# 4_ch_sample_and_hold.net
KiCad netlist of a schematic drawn in EAGLE
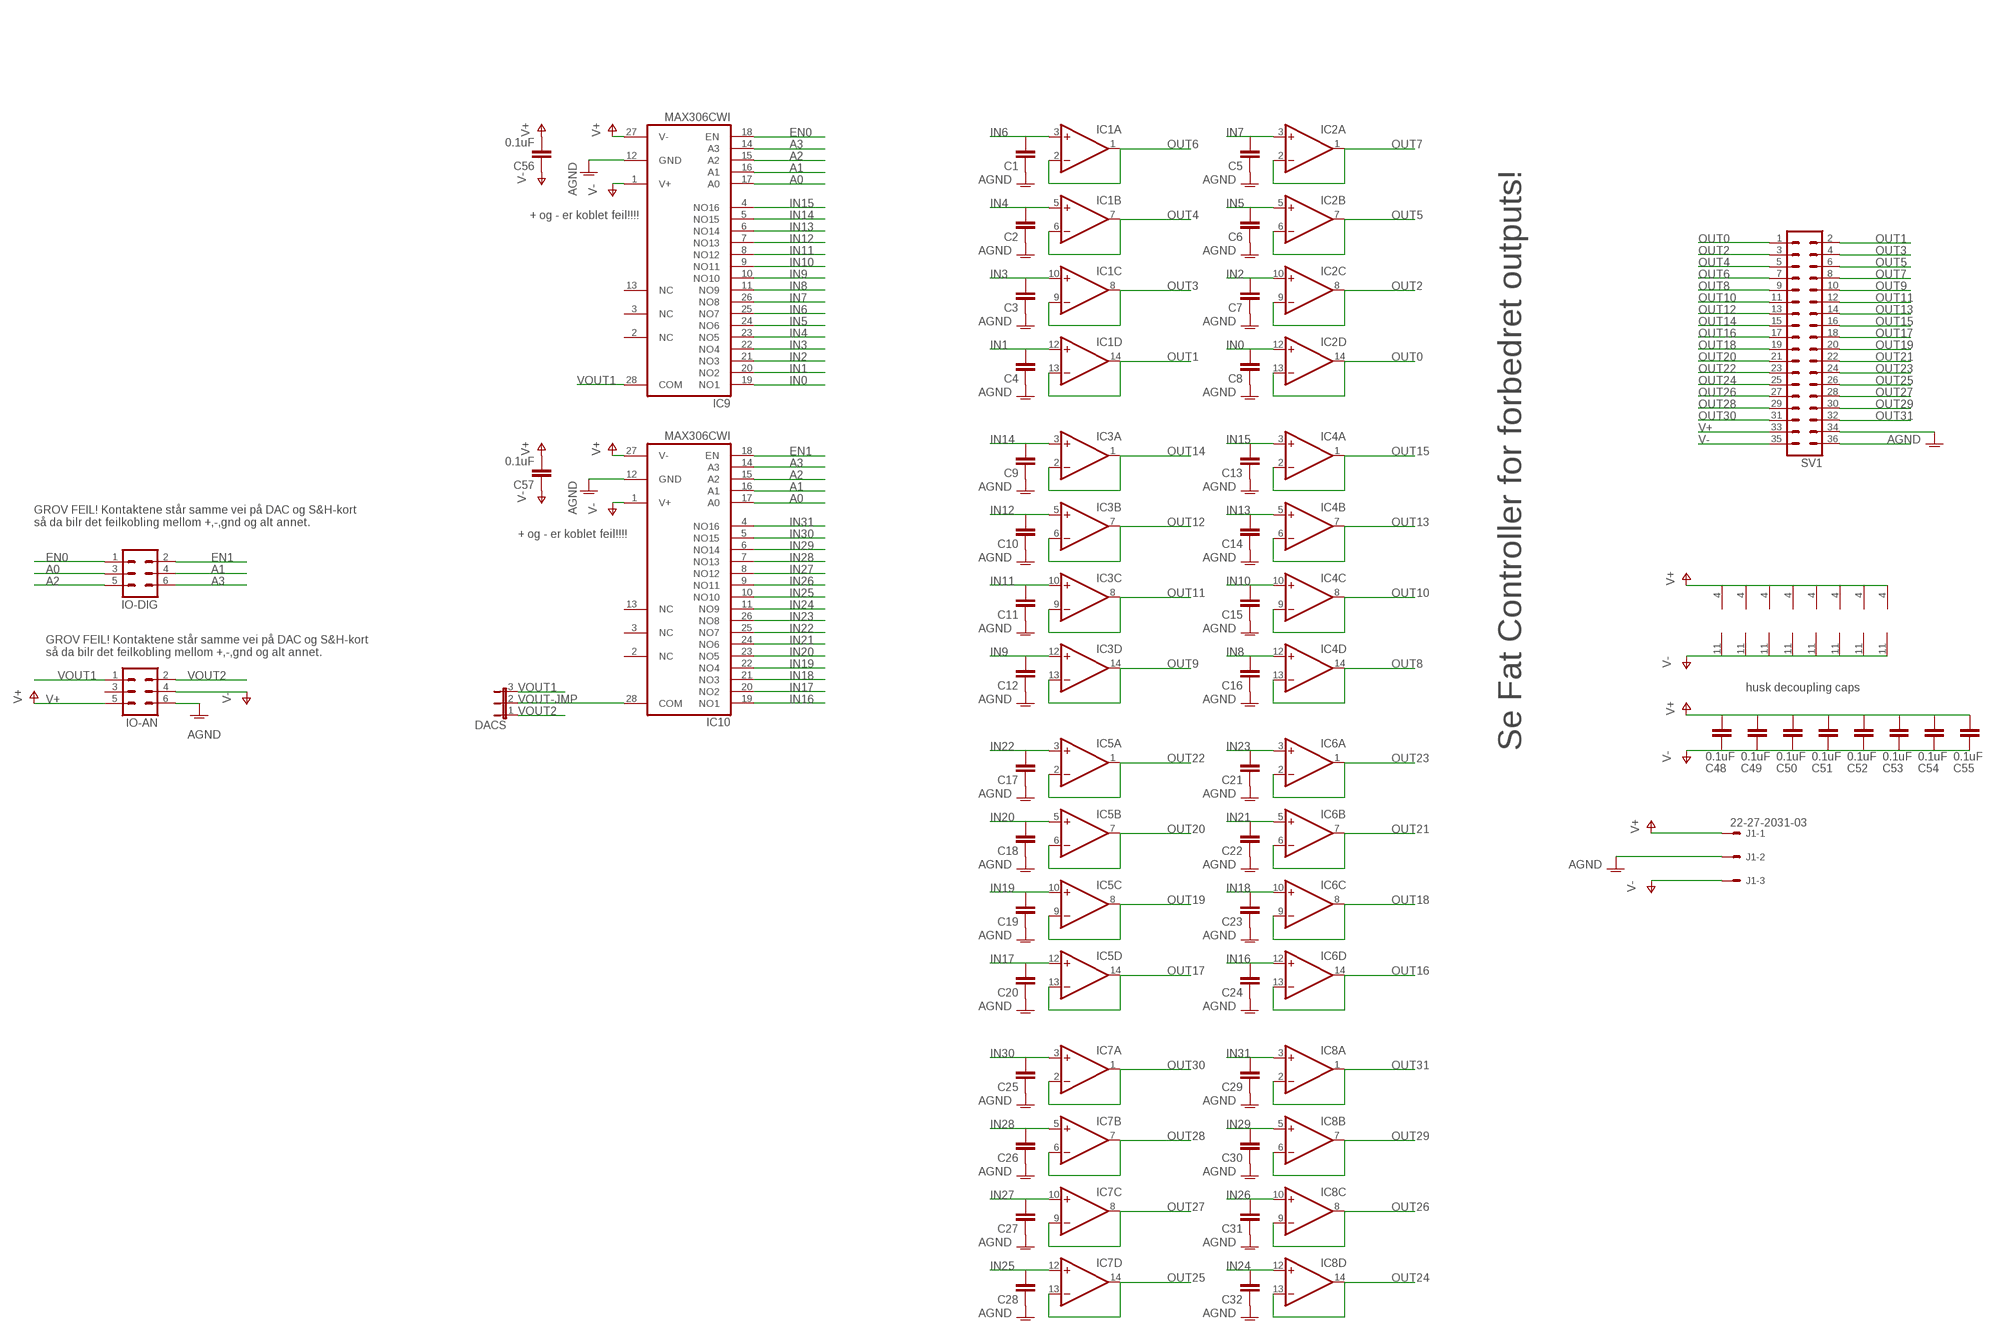
[diagram p0: schematic, sheet 1]

(export (version "E")
  (design (tool "Eeschema 10.0.6"))
  (components
    (comp (ref "C1")
      (value "C-EUC1206")
      (footprint "eagle-import:C1206")
      (libsource (lib "eagle-import") (part "C-EUC1206"))
    )
    (comp (ref "C2")
      (value "C-EUC1206")
      (footprint "eagle-import:C1206")
      (libsource (lib "eagle-import") (part "C-EUC1206"))
    )
    (comp (ref "C3")
      (value "C-EUC1206")
      (footprint "eagle-import:C1206")
      (libsource (lib "eagle-import") (part "C-EUC1206"))
    )
    (comp (ref "C4")
      (value "C-EUC1206")
      (footprint "eagle-import:C1206")
      (libsource (lib "eagle-import") (part "C-EUC1206"))
    )
    (comp (ref "C5")
      (value "C-EUC1206")
      (footprint "eagle-import:C1206")
      (libsource (lib "eagle-import") (part "C-EUC1206"))
    )
    (comp (ref "C6")
      (value "C-EUC1206")
      (footprint "eagle-import:C1206")
      (libsource (lib "eagle-import") (part "C-EUC1206"))
    )
    (comp (ref "C7")
      (value "C-EUC1206")
      (footprint "eagle-import:C1206")
      (libsource (lib "eagle-import") (part "C-EUC1206"))
    )
    (comp (ref "C8")
      (value "C-EUC1206")
      (footprint "eagle-import:C1206")
      (libsource (lib "eagle-import") (part "C-EUC1206"))
    )
    (comp (ref "C9")
      (value "C-EUC1206")
      (footprint "eagle-import:C1206")
      (libsource (lib "eagle-import") (part "C-EUC1206"))
    )
    (comp (ref "C10")
      (value "C-EUC1206")
      (footprint "eagle-import:C1206")
      (libsource (lib "eagle-import") (part "C-EUC1206"))
    )
    (comp (ref "C11")
      (value "C-EUC1206")
      (footprint "eagle-import:C1206")
      (libsource (lib "eagle-import") (part "C-EUC1206"))
    )
    (comp (ref "C12")
      (value "C-EUC1206")
      (footprint "eagle-import:C1206")
      (libsource (lib "eagle-import") (part "C-EUC1206"))
    )
    (comp (ref "C13")
      (value "C-EUC1206")
      (footprint "eagle-import:C1206")
      (libsource (lib "eagle-import") (part "C-EUC1206"))
    )
    (comp (ref "C14")
      (value "C-EUC1206")
      (footprint "eagle-import:C1206")
      (libsource (lib "eagle-import") (part "C-EUC1206"))
    )
    (comp (ref "C15")
      (value "C-EUC1206")
      (footprint "eagle-import:C1206")
      (libsource (lib "eagle-import") (part "C-EUC1206"))
    )
    (comp (ref "C16")
      (value "C-EUC1206")
      (footprint "eagle-import:C1206")
      (libsource (lib "eagle-import") (part "C-EUC1206"))
    )
    (comp (ref "C17")
      (value "C-EUC1206")
      (footprint "eagle-import:C1206")
      (libsource (lib "eagle-import") (part "C-EUC1206"))
    )
    (comp (ref "C18")
      (value "C-EUC1206")
      (footprint "eagle-import:C1206")
      (libsource (lib "eagle-import") (part "C-EUC1206"))
    )
    (comp (ref "C19")
      (value "C-EUC1206")
      (footprint "eagle-import:C1206")
      (libsource (lib "eagle-import") (part "C-EUC1206"))
    )
    (comp (ref "C20")
      (value "C-EUC1206")
      (footprint "eagle-import:C1206")
      (libsource (lib "eagle-import") (part "C-EUC1206"))
    )
    (comp (ref "C21")
      (value "C-EUC1206")
      (footprint "eagle-import:C1206")
      (libsource (lib "eagle-import") (part "C-EUC1206"))
    )
    (comp (ref "C22")
      (value "C-EUC1206")
      (footprint "eagle-import:C1206")
      (libsource (lib "eagle-import") (part "C-EUC1206"))
    )
    (comp (ref "C23")
      (value "C-EUC1206")
      (footprint "eagle-import:C1206")
      (libsource (lib "eagle-import") (part "C-EUC1206"))
    )
    (comp (ref "C24")
      (value "C-EUC1206")
      (footprint "eagle-import:C1206")
      (libsource (lib "eagle-import") (part "C-EUC1206"))
    )
    (comp (ref "C25")
      (value "C-EUC1206")
      (footprint "eagle-import:C1206")
      (libsource (lib "eagle-import") (part "C-EUC1206"))
    )
    (comp (ref "C26")
      (value "C-EUC1206")
      (footprint "eagle-import:C1206")
      (libsource (lib "eagle-import") (part "C-EUC1206"))
    )
    (comp (ref "C27")
      (value "C-EUC1206")
      (footprint "eagle-import:C1206")
      (libsource (lib "eagle-import") (part "C-EUC1206"))
    )
    (comp (ref "C28")
      (value "C-EUC1206")
      (footprint "eagle-import:C1206")
      (libsource (lib "eagle-import") (part "C-EUC1206"))
    )
    (comp (ref "C29")
      (value "C-EUC1206")
      (footprint "eagle-import:C1206")
      (libsource (lib "eagle-import") (part "C-EUC1206"))
    )
    (comp (ref "C30")
      (value "C-EUC1206")
      (footprint "eagle-import:C1206")
      (libsource (lib "eagle-import") (part "C-EUC1206"))
    )
    (comp (ref "C31")
      (value "C-EUC1206")
      (footprint "eagle-import:C1206")
      (libsource (lib "eagle-import") (part "C-EUC1206"))
    )
    (comp (ref "C32")
      (value "C-EUC1206")
      (footprint "eagle-import:C1206")
      (libsource (lib "eagle-import") (part "C-EUC1206"))
    )
    (comp (ref "C48")
      (value "0.1uF")
      (footprint "eagle-import:C0603")
      (libsource (lib "eagle-import") (part "C-EUC0603"))
    )
    (comp (ref "C49")
      (value "0.1uF")
      (footprint "eagle-import:C0603")
      (libsource (lib "eagle-import") (part "C-EUC0603"))
    )
    (comp (ref "C50")
      (value "0.1uF")
      (footprint "eagle-import:C0603")
      (libsource (lib "eagle-import") (part "C-EUC0603"))
    )
    (comp (ref "C51")
      (value "0.1uF")
      (footprint "eagle-import:C0603")
      (libsource (lib "eagle-import") (part "C-EUC0603"))
    )
    (comp (ref "C52")
      (value "0.1uF")
      (footprint "eagle-import:C0603")
      (libsource (lib "eagle-import") (part "C-EUC0603"))
    )
    (comp (ref "C53")
      (value "0.1uF")
      (footprint "eagle-import:C0603")
      (libsource (lib "eagle-import") (part "C-EUC0603"))
    )
    (comp (ref "C54")
      (value "0.1uF")
      (footprint "eagle-import:C0603")
      (libsource (lib "eagle-import") (part "C-EUC0603"))
    )
    (comp (ref "C55")
      (value "0.1uF")
      (footprint "eagle-import:C0603")
      (libsource (lib "eagle-import") (part "C-EUC0603"))
    )
    (comp (ref "C56")
      (value "0.1uF")
      (footprint "eagle-import:C0603")
      (libsource (lib "eagle-import") (part "C-EUC0603"))
    )
    (comp (ref "C57")
      (value "0.1uF")
      (footprint "eagle-import:C0603")
      (libsource (lib "eagle-import") (part "C-EUC0603"))
    )
    (comp (ref "DACS")
      (value "JP2E")
      (footprint "eagle-import:JP2")
      (libsource (lib "eagle-import") (part "JP2E"))
    )
    (comp (ref "IC1")
      (value "TL074D")
      (footprint "eagle-import:SO14")
      (libsource (lib "eagle-import") (part "TL074D"))
    )
    (comp (ref "IC2")
      (value "TL074D")
      (footprint "eagle-import:SO14")
      (libsource (lib "eagle-import") (part "TL074D"))
    )
    (comp (ref "IC3")
      (value "TL074D")
      (footprint "eagle-import:SO14")
      (libsource (lib "eagle-import") (part "TL074D"))
    )
    (comp (ref "IC4")
      (value "TL074D")
      (footprint "eagle-import:SO14")
      (libsource (lib "eagle-import") (part "TL074D"))
    )
    (comp (ref "IC5")
      (value "TL074D")
      (footprint "eagle-import:SO14")
      (libsource (lib "eagle-import") (part "TL074D"))
    )
    (comp (ref "IC6")
      (value "TL074D")
      (footprint "eagle-import:SO14")
      (libsource (lib "eagle-import") (part "TL074D"))
    )
    (comp (ref "IC7")
      (value "TL074D")
      (footprint "eagle-import:SO14")
      (libsource (lib "eagle-import") (part "TL074D"))
    )
    (comp (ref "IC8")
      (value "TL074D")
      (footprint "eagle-import:SO14")
      (libsource (lib "eagle-import") (part "TL074D"))
    )
    (comp (ref "IC9")
      (value "MAX306CWI")
      (footprint "eagle-import:SO28L")
      (fields (field (name "MF") "MAXIM"))
      (libsource (lib "eagle-import") (part "MAX306CWI"))
    )
    (comp (ref "IC10")
      (value "MAX306CWI")
      (footprint "eagle-import:SO28L")
      (fields (field (name "MF") "MAXIM"))
      (libsource (lib "eagle-import") (part "MAX306CWI"))
    )
    (comp (ref "IO-AN")
      (value "MA03-2")
      (footprint "eagle-import:MA03-2")
      (libsource (lib "eagle-import") (part "MA03-2"))
    )
    (comp (ref "IO-DIG")
      (value "MA03-2")
      (footprint "eagle-import:MA03-2")
      (libsource (lib "eagle-import") (part "MA03-2"))
    )
    (comp (ref "J1")
      (value "22-27-2031-03")
      (footprint "eagle-import:6410-03")
      (libsource (lib "eagle-import") (part "22-?-0327-2031"))
    )
    (comp (ref "SV1")
      (value "MA18-2")
      (footprint "eagle-import:MA18-2")
      (libsource (lib "eagle-import") (part "MA18-2"))
    )
  )
  (nets
    (net (code "1") (name "/A0") (class "Default")
      (node (ref "IC10") (pin "17") (pinfunction "A0_17") (pintype "input"))
      (node (ref "IC9") (pin "17") (pinfunction "A0_17") (pintype "input"))
      (node (ref "IO-DIG") (pin "3") (pinfunction "3_3") (pintype "passive"))
    )
    (net (code "2") (name "/A1") (class "Default")
      (node (ref "IC10") (pin "16") (pinfunction "A1_16") (pintype "input"))
      (node (ref "IC9") (pin "16") (pinfunction "A1_16") (pintype "input"))
      (node (ref "IO-DIG") (pin "4") (pinfunction "4_4") (pintype "passive"))
    )
    (net (code "3") (name "/A2") (class "Default")
      (node (ref "IC10") (pin "15") (pinfunction "A2_15") (pintype "input"))
      (node (ref "IC9") (pin "15") (pinfunction "A2_15") (pintype "input"))
      (node (ref "IO-DIG") (pin "5") (pinfunction "5_5") (pintype "passive"))
    )
    (net (code "4") (name "/A3") (class "Default")
      (node (ref "IC10") (pin "14") (pinfunction "A3_14") (pintype "input"))
      (node (ref "IC9") (pin "14") (pinfunction "A3_14") (pintype "input"))
      (node (ref "IO-DIG") (pin "6") (pinfunction "6_6") (pintype "passive"))
    )
    (net (code "5") (name "/EN0") (class "Default")
      (node (ref "IC9") (pin "18") (pinfunction "EN_18") (pintype "input"))
      (node (ref "IO-DIG") (pin "1") (pinfunction "1_1") (pintype "passive"))
    )
    (net (code "6") (name "/EN1") (class "Default")
      (node (ref "IC10") (pin "18") (pinfunction "EN_18") (pintype "input"))
      (node (ref "IO-DIG") (pin "2") (pinfunction "2_2") (pintype "passive"))
    )
    (net (code "7") (name "/IN0") (class "Default")
      (node (ref "C8") (pin "2") (pinfunction "2_2") (pintype "passive"))
      (node (ref "IC2") (pin "12") (pinfunction "+IN_12") (pintype "input"))
      (node (ref "IC9") (pin "19") (pinfunction "NO1_19") (pintype "passive"))
    )
    (net (code "8") (name "/IN1") (class "Default")
      (node (ref "C4") (pin "2") (pinfunction "2_2") (pintype "passive"))
      (node (ref "IC1") (pin "12") (pinfunction "+IN_12") (pintype "input"))
      (node (ref "IC9") (pin "20") (pinfunction "NO2_20") (pintype "passive"))
    )
    (net (code "9") (name "/IN2") (class "Default")
      (node (ref "C7") (pin "2") (pinfunction "2_2") (pintype "passive"))
      (node (ref "IC2") (pin "10") (pinfunction "+IN_10") (pintype "input"))
      (node (ref "IC9") (pin "21") (pinfunction "NO3_21") (pintype "passive"))
    )
    (net (code "10") (name "/IN3") (class "Default")
      (node (ref "C3") (pin "2") (pinfunction "2_2") (pintype "passive"))
      (node (ref "IC1") (pin "10") (pinfunction "+IN_10") (pintype "input"))
      (node (ref "IC9") (pin "22") (pinfunction "NO4_22") (pintype "passive"))
    )
    (net (code "11") (name "/IN4") (class "Default")
      (node (ref "C2") (pin "2") (pinfunction "2_2") (pintype "passive"))
      (node (ref "IC1") (pin "5") (pinfunction "+IN_5") (pintype "input"))
      (node (ref "IC9") (pin "23") (pinfunction "NO5_23") (pintype "passive"))
    )
    (net (code "12") (name "/IN5") (class "Default")
      (node (ref "C6") (pin "2") (pinfunction "2_2") (pintype "passive"))
      (node (ref "IC2") (pin "5") (pinfunction "+IN_5") (pintype "input"))
      (node (ref "IC9") (pin "24") (pinfunction "NO6_24") (pintype "passive"))
    )
    (net (code "13") (name "/IN6") (class "Default")
      (node (ref "C1") (pin "2") (pinfunction "2_2") (pintype "passive"))
      (node (ref "IC1") (pin "3") (pinfunction "+IN_3") (pintype "input"))
      (node (ref "IC9") (pin "25") (pinfunction "NO7_25") (pintype "passive"))
    )
    (net (code "14") (name "/IN7") (class "Default")
      (node (ref "C5") (pin "2") (pinfunction "2_2") (pintype "passive"))
      (node (ref "IC2") (pin "3") (pinfunction "+IN_3") (pintype "input"))
      (node (ref "IC9") (pin "26") (pinfunction "NO8_26") (pintype "passive"))
    )
    (net (code "15") (name "/IN8") (class "Default")
      (node (ref "C16") (pin "2") (pinfunction "2_2") (pintype "passive"))
      (node (ref "IC4") (pin "12") (pinfunction "+IN_12") (pintype "input"))
      (node (ref "IC9") (pin "11") (pinfunction "NO9_11") (pintype "passive"))
    )
    (net (code "16") (name "/IN9") (class "Default")
      (node (ref "C12") (pin "2") (pinfunction "2_2") (pintype "passive"))
      (node (ref "IC3") (pin "12") (pinfunction "+IN_12") (pintype "input"))
      (node (ref "IC9") (pin "10") (pinfunction "NO10_10") (pintype "passive"))
    )
    (net (code "17") (name "/IN10") (class "Default")
      (node (ref "C15") (pin "2") (pinfunction "2_2") (pintype "passive"))
      (node (ref "IC4") (pin "10") (pinfunction "+IN_10") (pintype "input"))
      (node (ref "IC9") (pin "9") (pinfunction "NO11_9") (pintype "passive"))
    )
    (net (code "18") (name "/IN11") (class "Default")
      (node (ref "C11") (pin "2") (pinfunction "2_2") (pintype "passive"))
      (node (ref "IC3") (pin "10") (pinfunction "+IN_10") (pintype "input"))
      (node (ref "IC9") (pin "8") (pinfunction "NO12_8") (pintype "passive"))
    )
    (net (code "19") (name "/IN12") (class "Default")
      (node (ref "C10") (pin "2") (pinfunction "2_2") (pintype "passive"))
      (node (ref "IC3") (pin "5") (pinfunction "+IN_5") (pintype "input"))
      (node (ref "IC9") (pin "7") (pinfunction "NO13_7") (pintype "passive"))
    )
    (net (code "20") (name "/IN13") (class "Default")
      (node (ref "C14") (pin "2") (pinfunction "2_2") (pintype "passive"))
      (node (ref "IC4") (pin "5") (pinfunction "+IN_5") (pintype "input"))
      (node (ref "IC9") (pin "6") (pinfunction "NO14_6") (pintype "passive"))
    )
    (net (code "21") (name "/IN14") (class "Default")
      (node (ref "C9") (pin "2") (pinfunction "2_2") (pintype "passive"))
      (node (ref "IC3") (pin "3") (pinfunction "+IN_3") (pintype "input"))
      (node (ref "IC9") (pin "5") (pinfunction "NO15_5") (pintype "passive"))
    )
    (net (code "22") (name "/IN15") (class "Default")
      (node (ref "C13") (pin "2") (pinfunction "2_2") (pintype "passive"))
      (node (ref "IC4") (pin "3") (pinfunction "+IN_3") (pintype "input"))
      (node (ref "IC9") (pin "4") (pinfunction "NO16_4") (pintype "passive"))
    )
    (net (code "23") (name "/IN16") (class "Default")
      (node (ref "C24") (pin "2") (pinfunction "2_2") (pintype "passive"))
      (node (ref "IC10") (pin "19") (pinfunction "NO1_19") (pintype "passive"))
      (node (ref "IC6") (pin "12") (pinfunction "+IN_12") (pintype "input"))
    )
    (net (code "24") (name "/IN17") (class "Default")
      (node (ref "C20") (pin "2") (pinfunction "2_2") (pintype "passive"))
      (node (ref "IC10") (pin "20") (pinfunction "NO2_20") (pintype "passive"))
      (node (ref "IC5") (pin "12") (pinfunction "+IN_12") (pintype "input"))
    )
    (net (code "25") (name "/IN18") (class "Default")
      (node (ref "C23") (pin "2") (pinfunction "2_2") (pintype "passive"))
      (node (ref "IC10") (pin "21") (pinfunction "NO3_21") (pintype "passive"))
      (node (ref "IC6") (pin "10") (pinfunction "+IN_10") (pintype "input"))
    )
    (net (code "26") (name "/IN19") (class "Default")
      (node (ref "C19") (pin "2") (pinfunction "2_2") (pintype "passive"))
      (node (ref "IC10") (pin "22") (pinfunction "NO4_22") (pintype "passive"))
      (node (ref "IC5") (pin "10") (pinfunction "+IN_10") (pintype "input"))
    )
    (net (code "27") (name "/IN20") (class "Default")
      (node (ref "C18") (pin "2") (pinfunction "2_2") (pintype "passive"))
      (node (ref "IC10") (pin "23") (pinfunction "NO5_23") (pintype "passive"))
      (node (ref "IC5") (pin "5") (pinfunction "+IN_5") (pintype "input"))
    )
    (net (code "28") (name "/IN21") (class "Default")
      (node (ref "C22") (pin "2") (pinfunction "2_2") (pintype "passive"))
      (node (ref "IC10") (pin "24") (pinfunction "NO6_24") (pintype "passive"))
      (node (ref "IC6") (pin "5") (pinfunction "+IN_5") (pintype "input"))
    )
    (net (code "29") (name "/IN22") (class "Default")
      (node (ref "C17") (pin "2") (pinfunction "2_2") (pintype "passive"))
      (node (ref "IC10") (pin "25") (pinfunction "NO7_25") (pintype "passive"))
      (node (ref "IC5") (pin "3") (pinfunction "+IN_3") (pintype "input"))
    )
    (net (code "30") (name "/IN23") (class "Default")
      (node (ref "C21") (pin "2") (pinfunction "2_2") (pintype "passive"))
      (node (ref "IC10") (pin "26") (pinfunction "NO8_26") (pintype "passive"))
      (node (ref "IC6") (pin "3") (pinfunction "+IN_3") (pintype "input"))
    )
    (net (code "31") (name "/IN24") (class "Default")
      (node (ref "C32") (pin "2") (pinfunction "2_2") (pintype "passive"))
      (node (ref "IC10") (pin "11") (pinfunction "NO9_11") (pintype "passive"))
      (node (ref "IC8") (pin "12") (pinfunction "+IN_12") (pintype "input"))
    )
    (net (code "32") (name "/IN25") (class "Default")
      (node (ref "C28") (pin "2") (pinfunction "2_2") (pintype "passive"))
      (node (ref "IC10") (pin "10") (pinfunction "NO10_10") (pintype "passive"))
      (node (ref "IC7") (pin "12") (pinfunction "+IN_12") (pintype "input"))
    )
    (net (code "33") (name "/IN26") (class "Default")
      (node (ref "C31") (pin "2") (pinfunction "2_2") (pintype "passive"))
      (node (ref "IC10") (pin "9") (pinfunction "NO11_9") (pintype "passive"))
      (node (ref "IC8") (pin "10") (pinfunction "+IN_10") (pintype "input"))
    )
    (net (code "34") (name "/IN27") (class "Default")
      (node (ref "C27") (pin "2") (pinfunction "2_2") (pintype "passive"))
      (node (ref "IC10") (pin "8") (pinfunction "NO12_8") (pintype "passive"))
      (node (ref "IC7") (pin "10") (pinfunction "+IN_10") (pintype "input"))
    )
    (net (code "35") (name "/IN28") (class "Default")
      (node (ref "C26") (pin "2") (pinfunction "2_2") (pintype "passive"))
      (node (ref "IC10") (pin "7") (pinfunction "NO13_7") (pintype "passive"))
      (node (ref "IC7") (pin "5") (pinfunction "+IN_5") (pintype "input"))
    )
    (net (code "36") (name "/IN29") (class "Default")
      (node (ref "C30") (pin "2") (pinfunction "2_2") (pintype "passive"))
      (node (ref "IC10") (pin "6") (pinfunction "NO14_6") (pintype "passive"))
      (node (ref "IC8") (pin "5") (pinfunction "+IN_5") (pintype "input"))
    )
    (net (code "37") (name "/IN30") (class "Default")
      (node (ref "C25") (pin "2") (pinfunction "2_2") (pintype "passive"))
      (node (ref "IC10") (pin "5") (pinfunction "NO15_5") (pintype "passive"))
      (node (ref "IC7") (pin "3") (pinfunction "+IN_3") (pintype "input"))
    )
    (net (code "38") (name "/IN31") (class "Default")
      (node (ref "C29") (pin "2") (pinfunction "2_2") (pintype "passive"))
      (node (ref "IC10") (pin "4") (pinfunction "NO16_4") (pintype "passive"))
      (node (ref "IC8") (pin "3") (pinfunction "+IN_3") (pintype "input"))
    )
    (net (code "39") (name "/OUT0") (class "Default")
      (node (ref "IC2") (pin "13") (pinfunction "-IN_13") (pintype "input"))
      (node (ref "IC2") (pin "14") (pinfunction "OUT_14") (pintype "output"))
      (node (ref "SV1") (pin "1") (pinfunction "1_1") (pintype "passive"))
    )
    (net (code "40") (name "/OUT1") (class "Default")
      (node (ref "IC1") (pin "13") (pinfunction "-IN_13") (pintype "input"))
      (node (ref "IC1") (pin "14") (pinfunction "OUT_14") (pintype "output"))
      (node (ref "SV1") (pin "2") (pinfunction "2_2") (pintype "passive"))
    )
    (net (code "41") (name "/OUT2") (class "Default")
      (node (ref "IC2") (pin "8") (pinfunction "OUT_8") (pintype "output"))
      (node (ref "IC2") (pin "9") (pinfunction "-IN_9") (pintype "input"))
      (node (ref "SV1") (pin "3") (pinfunction "3_3") (pintype "passive"))
    )
    (net (code "42") (name "/OUT3") (class "Default")
      (node (ref "IC1") (pin "8") (pinfunction "OUT_8") (pintype "output"))
      (node (ref "IC1") (pin "9") (pinfunction "-IN_9") (pintype "input"))
      (node (ref "SV1") (pin "4") (pinfunction "4_4") (pintype "passive"))
    )
    (net (code "43") (name "/OUT4") (class "Default")
      (node (ref "IC1") (pin "6") (pinfunction "-IN_6") (pintype "input"))
      (node (ref "IC1") (pin "7") (pinfunction "OUT_7") (pintype "output"))
      (node (ref "SV1") (pin "5") (pinfunction "5_5") (pintype "passive"))
    )
    (net (code "44") (name "/OUT5") (class "Default")
      (node (ref "IC2") (pin "6") (pinfunction "-IN_6") (pintype "input"))
      (node (ref "IC2") (pin "7") (pinfunction "OUT_7") (pintype "output"))
      (node (ref "SV1") (pin "6") (pinfunction "6_6") (pintype "passive"))
    )
    (net (code "45") (name "/OUT6") (class "Default")
      (node (ref "IC1") (pin "1") (pinfunction "OUT_1") (pintype "output"))
      (node (ref "IC1") (pin "2") (pinfunction "-IN_2") (pintype "input"))
      (node (ref "SV1") (pin "7") (pinfunction "7_7") (pintype "passive"))
    )
    (net (code "46") (name "/OUT7") (class "Default")
      (node (ref "IC2") (pin "1") (pinfunction "OUT_1") (pintype "output"))
      (node (ref "IC2") (pin "2") (pinfunction "-IN_2") (pintype "input"))
      (node (ref "SV1") (pin "8") (pinfunction "8_8") (pintype "passive"))
    )
    (net (code "47") (name "/OUT8") (class "Default")
      (node (ref "IC4") (pin "13") (pinfunction "-IN_13") (pintype "input"))
      (node (ref "IC4") (pin "14") (pinfunction "OUT_14") (pintype "output"))
      (node (ref "SV1") (pin "9") (pinfunction "9_9") (pintype "passive"))
    )
    (net (code "48") (name "/OUT9") (class "Default")
      (node (ref "IC3") (pin "13") (pinfunction "-IN_13") (pintype "input"))
      (node (ref "IC3") (pin "14") (pinfunction "OUT_14") (pintype "output"))
      (node (ref "SV1") (pin "10") (pinfunction "10_10") (pintype "passive"))
    )
    (net (code "49") (name "/OUT10") (class "Default")
      (node (ref "IC4") (pin "8") (pinfunction "OUT_8") (pintype "output"))
      (node (ref "IC4") (pin "9") (pinfunction "-IN_9") (pintype "input"))
      (node (ref "SV1") (pin "11") (pinfunction "11_11") (pintype "passive"))
    )
    (net (code "50") (name "/OUT11") (class "Default")
      (node (ref "IC3") (pin "8") (pinfunction "OUT_8") (pintype "output"))
      (node (ref "IC3") (pin "9") (pinfunction "-IN_9") (pintype "input"))
      (node (ref "SV1") (pin "12") (pinfunction "12_12") (pintype "passive"))
    )
    (net (code "51") (name "/OUT12") (class "Default")
      (node (ref "IC3") (pin "6") (pinfunction "-IN_6") (pintype "input"))
      (node (ref "IC3") (pin "7") (pinfunction "OUT_7") (pintype "output"))
      (node (ref "SV1") (pin "13") (pinfunction "13_13") (pintype "passive"))
    )
    (net (code "52") (name "/OUT13") (class "Default")
      (node (ref "IC4") (pin "6") (pinfunction "-IN_6") (pintype "input"))
      (node (ref "IC4") (pin "7") (pinfunction "OUT_7") (pintype "output"))
      (node (ref "SV1") (pin "14") (pinfunction "14_14") (pintype "passive"))
    )
    (net (code "53") (name "/OUT14") (class "Default")
      (node (ref "IC3") (pin "1") (pinfunction "OUT_1") (pintype "output"))
      (node (ref "IC3") (pin "2") (pinfunction "-IN_2") (pintype "input"))
      (node (ref "SV1") (pin "15") (pinfunction "15_15") (pintype "passive"))
    )
    (net (code "54") (name "/OUT15") (class "Default")
      (node (ref "IC4") (pin "1") (pinfunction "OUT_1") (pintype "output"))
      (node (ref "IC4") (pin "2") (pinfunction "-IN_2") (pintype "input"))
      (node (ref "SV1") (pin "16") (pinfunction "16_16") (pintype "passive"))
    )
    (net (code "55") (name "/OUT16") (class "Default")
      (node (ref "IC6") (pin "13") (pinfunction "-IN_13") (pintype "input"))
      (node (ref "IC6") (pin "14") (pinfunction "OUT_14") (pintype "output"))
      (node (ref "SV1") (pin "17") (pinfunction "17_17") (pintype "passive"))
    )
    (net (code "56") (name "/OUT17") (class "Default")
      (node (ref "IC5") (pin "13") (pinfunction "-IN_13") (pintype "input"))
      (node (ref "IC5") (pin "14") (pinfunction "OUT_14") (pintype "output"))
      (node (ref "SV1") (pin "18") (pinfunction "18_18") (pintype "passive"))
    )
    (net (code "57") (name "/OUT18") (class "Default")
      (node (ref "IC6") (pin "8") (pinfunction "OUT_8") (pintype "output"))
      (node (ref "IC6") (pin "9") (pinfunction "-IN_9") (pintype "input"))
      (node (ref "SV1") (pin "19") (pinfunction "19_19") (pintype "passive"))
    )
    (net (code "58") (name "/OUT19") (class "Default")
      (node (ref "IC5") (pin "8") (pinfunction "OUT_8") (pintype "output"))
      (node (ref "IC5") (pin "9") (pinfunction "-IN_9") (pintype "input"))
      (node (ref "SV1") (pin "20") (pinfunction "20_20") (pintype "passive"))
    )
    (net (code "59") (name "/OUT20") (class "Default")
      (node (ref "IC5") (pin "6") (pinfunction "-IN_6") (pintype "input"))
      (node (ref "IC5") (pin "7") (pinfunction "OUT_7") (pintype "output"))
      (node (ref "SV1") (pin "21") (pinfunction "21_21") (pintype "passive"))
    )
    (net (code "60") (name "/OUT21") (class "Default")
      (node (ref "IC6") (pin "6") (pinfunction "-IN_6") (pintype "input"))
      (node (ref "IC6") (pin "7") (pinfunction "OUT_7") (pintype "output"))
      (node (ref "SV1") (pin "22") (pinfunction "22_22") (pintype "passive"))
    )
    (net (code "61") (name "/OUT22") (class "Default")
      (node (ref "IC5") (pin "1") (pinfunction "OUT_1") (pintype "output"))
      (node (ref "IC5") (pin "2") (pinfunction "-IN_2") (pintype "input"))
      (node (ref "SV1") (pin "23") (pinfunction "23_23") (pintype "passive"))
    )
    (net (code "62") (name "/OUT23") (class "Default")
      (node (ref "IC6") (pin "1") (pinfunction "OUT_1") (pintype "output"))
      (node (ref "IC6") (pin "2") (pinfunction "-IN_2") (pintype "input"))
      (node (ref "SV1") (pin "24") (pinfunction "24_24") (pintype "passive"))
    )
    (net (code "63") (name "/OUT24") (class "Default")
      (node (ref "IC8") (pin "13") (pinfunction "-IN_13") (pintype "input"))
      (node (ref "IC8") (pin "14") (pinfunction "OUT_14") (pintype "output"))
      (node (ref "SV1") (pin "25") (pinfunction "25_25") (pintype "passive"))
    )
    (net (code "64") (name "/OUT25") (class "Default")
      (node (ref "IC7") (pin "13") (pinfunction "-IN_13") (pintype "input"))
      (node (ref "IC7") (pin "14") (pinfunction "OUT_14") (pintype "output"))
      (node (ref "SV1") (pin "26") (pinfunction "26_26") (pintype "passive"))
    )
    (net (code "65") (name "/OUT26") (class "Default")
      (node (ref "IC8") (pin "8") (pinfunction "OUT_8") (pintype "output"))
      (node (ref "IC8") (pin "9") (pinfunction "-IN_9") (pintype "input"))
      (node (ref "SV1") (pin "27") (pinfunction "27_27") (pintype "passive"))
    )
    (net (code "66") (name "/OUT27") (class "Default")
      (node (ref "IC7") (pin "8") (pinfunction "OUT_8") (pintype "output"))
      (node (ref "IC7") (pin "9") (pinfunction "-IN_9") (pintype "input"))
      (node (ref "SV1") (pin "28") (pinfunction "28_28") (pintype "passive"))
    )
    (net (code "67") (name "/OUT28") (class "Default")
      (node (ref "IC7") (pin "6") (pinfunction "-IN_6") (pintype "input"))
      (node (ref "IC7") (pin "7") (pinfunction "OUT_7") (pintype "output"))
      (node (ref "SV1") (pin "29") (pinfunction "29_29") (pintype "passive"))
    )
    (net (code "68") (name "/OUT29") (class "Default")
      (node (ref "IC8") (pin "6") (pinfunction "-IN_6") (pintype "input"))
      (node (ref "IC8") (pin "7") (pinfunction "OUT_7") (pintype "output"))
      (node (ref "SV1") (pin "30") (pinfunction "30_30") (pintype "passive"))
    )
    (net (code "69") (name "/OUT30") (class "Default")
      (node (ref "IC7") (pin "1") (pinfunction "OUT_1") (pintype "output"))
      (node (ref "IC7") (pin "2") (pinfunction "-IN_2") (pintype "input"))
      (node (ref "SV1") (pin "31") (pinfunction "31_31") (pintype "passive"))
    )
    (net (code "70") (name "/OUT31") (class "Default")
      (node (ref "IC8") (pin "1") (pinfunction "OUT_1") (pintype "output"))
      (node (ref "IC8") (pin "2") (pinfunction "-IN_2") (pintype "input"))
      (node (ref "SV1") (pin "32") (pinfunction "32_32") (pintype "passive"))
    )
    (net (code "71") (name "/VOUT-JMP") (class "Default")
      (node (ref "DACS") (pin "2") (pinfunction "2_2") (pintype "passive"))
      (node (ref "IC10") (pin "28") (pinfunction "COM_28") (pintype "passive"))
    )
    (net (code "72") (name "/VOUT1") (class "Default")
      (node (ref "DACS") (pin "3") (pinfunction "3_3") (pintype "passive"))
      (node (ref "IC9") (pin "28") (pinfunction "COM_28") (pintype "passive"))
      (node (ref "IO-AN") (pin "1") (pinfunction "1_1") (pintype "passive"))
    )
    (net (code "73") (name "/VOUT2") (class "Default")
      (node (ref "DACS") (pin "1") (pinfunction "1_1") (pintype "passive"))
      (node (ref "IO-AN") (pin "2") (pinfunction "2_2") (pintype "passive"))
    )
    (net (code "74") (name "AGND") (class "Default")
      (node (ref "C1") (pin "1") (pinfunction "1_1") (pintype "passive"))
      (node (ref "C10") (pin "1") (pinfunction "1_1") (pintype "passive"))
      (node (ref "C11") (pin "1") (pinfunction "1_1") (pintype "passive"))
      (node (ref "C12") (pin "1") (pinfunction "1_1") (pintype "passive"))
      (node (ref "C13") (pin "1") (pinfunction "1_1") (pintype "passive"))
      (node (ref "C14") (pin "1") (pinfunction "1_1") (pintype "passive"))
      (node (ref "C15") (pin "1") (pinfunction "1_1") (pintype "passive"))
      (node (ref "C16") (pin "1") (pinfunction "1_1") (pintype "passive"))
      (node (ref "C17") (pin "1") (pinfunction "1_1") (pintype "passive"))
      (node (ref "C18") (pin "1") (pinfunction "1_1") (pintype "passive"))
      (node (ref "C19") (pin "1") (pinfunction "1_1") (pintype "passive"))
      (node (ref "C2") (pin "1") (pinfunction "1_1") (pintype "passive"))
      (node (ref "C20") (pin "1") (pinfunction "1_1") (pintype "passive"))
      (node (ref "C21") (pin "1") (pinfunction "1_1") (pintype "passive"))
      (node (ref "C22") (pin "1") (pinfunction "1_1") (pintype "passive"))
      (node (ref "C23") (pin "1") (pinfunction "1_1") (pintype "passive"))
      (node (ref "C24") (pin "1") (pinfunction "1_1") (pintype "passive"))
      (node (ref "C25") (pin "1") (pinfunction "1_1") (pintype "passive"))
      (node (ref "C26") (pin "1") (pinfunction "1_1") (pintype "passive"))
      (node (ref "C27") (pin "1") (pinfunction "1_1") (pintype "passive"))
      (node (ref "C28") (pin "1") (pinfunction "1_1") (pintype "passive"))
      (node (ref "C29") (pin "1") (pinfunction "1_1") (pintype "passive"))
      (node (ref "C3") (pin "1") (pinfunction "1_1") (pintype "passive"))
      (node (ref "C30") (pin "1") (pinfunction "1_1") (pintype "passive"))
      (node (ref "C31") (pin "1") (pinfunction "1_1") (pintype "passive"))
      (node (ref "C32") (pin "1") (pinfunction "1_1") (pintype "passive"))
      (node (ref "C4") (pin "1") (pinfunction "1_1") (pintype "passive"))
      (node (ref "C5") (pin "1") (pinfunction "1_1") (pintype "passive"))
      (node (ref "C6") (pin "1") (pinfunction "1_1") (pintype "passive"))
      (node (ref "C7") (pin "1") (pinfunction "1_1") (pintype "passive"))
      (node (ref "C8") (pin "1") (pinfunction "1_1") (pintype "passive"))
      (node (ref "C9") (pin "1") (pinfunction "1_1") (pintype "passive"))
      (node (ref "IC10") (pin "12") (pinfunction "GND_12") (pintype "power_in"))
      (node (ref "IC9") (pin "12") (pinfunction "GND_12") (pintype "power_in"))
      (node (ref "IO-AN") (pin "6") (pinfunction "6_6") (pintype "passive"))
      (node (ref "J1") (pin "2") (pinfunction "S_2") (pintype "passive"))
      (node (ref "SV1") (pin "34") (pinfunction "34_34") (pintype "passive"))
    )
    (net (code "75") (name "V+") (class "Default")
      (node (ref "C48") (pin "2") (pinfunction "2_2") (pintype "passive"))
      (node (ref "C49") (pin "2") (pinfunction "2_2") (pintype "passive"))
      (node (ref "C50") (pin "2") (pinfunction "2_2") (pintype "passive"))
      (node (ref "C51") (pin "2") (pinfunction "2_2") (pintype "passive"))
      (node (ref "C52") (pin "2") (pinfunction "2_2") (pintype "passive"))
      (node (ref "C53") (pin "2") (pinfunction "2_2") (pintype "passive"))
      (node (ref "C54") (pin "2") (pinfunction "2_2") (pintype "passive"))
      (node (ref "C55") (pin "2") (pinfunction "2_2") (pintype "passive"))
      (node (ref "C56") (pin "2") (pinfunction "2_2") (pintype "passive"))
      (node (ref "C57") (pin "2") (pinfunction "2_2") (pintype "passive"))
      (node (ref "IC1") (pin "4") (pinfunction "V+_4") (pintype "power_in"))
      (node (ref "IC10") (pin "27") (pinfunction "V-_27") (pintype "power_in"))
      (node (ref "IC2") (pin "4") (pinfunction "V+_4") (pintype "power_in"))
      (node (ref "IC3") (pin "4") (pinfunction "V+_4") (pintype "power_in"))
      (node (ref "IC4") (pin "4") (pinfunction "V+_4") (pintype "power_in"))
      (node (ref "IC5") (pin "4") (pinfunction "V+_4") (pintype "power_in"))
      (node (ref "IC6") (pin "4") (pinfunction "V+_4") (pintype "power_in"))
      (node (ref "IC7") (pin "4") (pinfunction "V+_4") (pintype "power_in"))
      (node (ref "IC8") (pin "4") (pinfunction "V+_4") (pintype "power_in"))
      (node (ref "IC9") (pin "27") (pinfunction "V-_27") (pintype "power_in"))
      (node (ref "IO-AN") (pin "5") (pinfunction "5_5") (pintype "passive"))
      (node (ref "J1") (pin "1") (pinfunction "S_1") (pintype "passive"))
      (node (ref "SV1") (pin "33") (pinfunction "33_33") (pintype "passive"))
    )
    (net (code "76") (name "V-") (class "Default")
      (node (ref "C48") (pin "1") (pinfunction "1_1") (pintype "passive"))
      (node (ref "C49") (pin "1") (pinfunction "1_1") (pintype "passive"))
      (node (ref "C50") (pin "1") (pinfunction "1_1") (pintype "passive"))
      (node (ref "C51") (pin "1") (pinfunction "1_1") (pintype "passive"))
      (node (ref "C52") (pin "1") (pinfunction "1_1") (pintype "passive"))
      (node (ref "C53") (pin "1") (pinfunction "1_1") (pintype "passive"))
      (node (ref "C54") (pin "1") (pinfunction "1_1") (pintype "passive"))
      (node (ref "C55") (pin "1") (pinfunction "1_1") (pintype "passive"))
      (node (ref "C56") (pin "1") (pinfunction "1_1") (pintype "passive"))
      (node (ref "C57") (pin "1") (pinfunction "1_1") (pintype "passive"))
      (node (ref "IC1") (pin "11") (pinfunction "V-_11") (pintype "power_in"))
      (node (ref "IC10") (pin "1") (pinfunction "V+_1") (pintype "power_in"))
      (node (ref "IC2") (pin "11") (pinfunction "V-_11") (pintype "power_in"))
      (node (ref "IC3") (pin "11") (pinfunction "V-_11") (pintype "power_in"))
      (node (ref "IC4") (pin "11") (pinfunction "V-_11") (pintype "power_in"))
      (node (ref "IC5") (pin "11") (pinfunction "V-_11") (pintype "power_in"))
      (node (ref "IC6") (pin "11") (pinfunction "V-_11") (pintype "power_in"))
      (node (ref "IC7") (pin "11") (pinfunction "V-_11") (pintype "power_in"))
      (node (ref "IC8") (pin "11") (pinfunction "V-_11") (pintype "power_in"))
      (node (ref "IC9") (pin "1") (pinfunction "V+_1") (pintype "power_in"))
      (node (ref "IO-AN") (pin "4") (pinfunction "4_4") (pintype "passive"))
      (node (ref "J1") (pin "3") (pinfunction "S_3") (pintype "passive"))
      (node (ref "SV1") (pin "35") (pinfunction "35_35") (pintype "passive"))
    )
    (net (code "77") (name "unconnected-(IC9-NC-Pad2)") (class "Default")
      (node (ref "IC9") (pin "2") (pinfunction "NC_2") (pintype "no_connect"))
    )
    (net (code "78") (name "unconnected-(IC9-NC-Pad3)") (class "Default")
      (node (ref "IC9") (pin "3") (pinfunction "NC_3") (pintype "no_connect"))
    )
    (net (code "79") (name "unconnected-(IC9-NC-Pad13)") (class "Default")
      (node (ref "IC9") (pin "13") (pinfunction "NC_13") (pintype "no_connect"))
    )
    (net (code "80") (name "unconnected-(IC10-NC-Pad2)") (class "Default")
      (node (ref "IC10") (pin "2") (pinfunction "NC_2") (pintype "no_connect"))
    )
    (net (code "81") (name "unconnected-(IC10-NC-Pad3)") (class "Default")
      (node (ref "IC10") (pin "3") (pinfunction "NC_3") (pintype "no_connect"))
    )
    (net (code "82") (name "unconnected-(IC10-NC-Pad13)") (class "Default")
      (node (ref "IC10") (pin "13") (pinfunction "NC_13") (pintype "no_connect"))
    )
    (net (code "83") (name "unconnected-(IO-AN-Pad3)") (class "Default")
      (node (ref "IO-AN") (pin "3") (pinfunction "3_3") (pintype "passive"))
    )
    (net (code "84") (name "unconnected-(SV1-Pad36)") (class "Default")
      (node (ref "SV1") (pin "36") (pinfunction "36_36") (pintype "passive"))
    )
  )
)
